# FlashLight.net
KiCad netlist of a schematic drawn in EAGLE
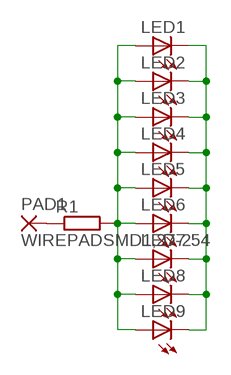
[diagram p0: schematic, sheet 1]

(export (version "E")
  (design (tool "Eeschema 10.0.6"))
  (components
    (comp (ref "LED1")
      (value "LED5MM")
      (footprint "eagle-import:LED5MM")
      (libsource (lib "eagle-import") (part "LED5MM"))
    )
    (comp (ref "LED2")
      (value "LED5MM")
      (footprint "eagle-import:LED5MM")
      (libsource (lib "eagle-import") (part "LED5MM"))
    )
    (comp (ref "LED3")
      (value "LED5MM")
      (footprint "eagle-import:LED5MM")
      (libsource (lib "eagle-import") (part "LED5MM"))
    )
    (comp (ref "LED4")
      (value "LED5MM")
      (footprint "eagle-import:LED5MM")
      (libsource (lib "eagle-import") (part "LED5MM"))
    )
    (comp (ref "LED5")
      (value "LED5MM")
      (footprint "eagle-import:LED5MM")
      (libsource (lib "eagle-import") (part "LED5MM"))
    )
    (comp (ref "LED6")
      (value "LED5MM")
      (footprint "eagle-import:LED5MM")
      (libsource (lib "eagle-import") (part "LED5MM"))
    )
    (comp (ref "LED7")
      (value "LED5MM")
      (footprint "eagle-import:LED5MM")
      (libsource (lib "eagle-import") (part "LED5MM"))
    )
    (comp (ref "LED8")
      (value "LED5MM")
      (footprint "eagle-import:LED5MM")
      (libsource (lib "eagle-import") (part "LED5MM"))
    )
    (comp (ref "LED9")
      (value "LED5MM")
      (footprint "eagle-import:LED5MM")
      (libsource (lib "eagle-import") (part "LED5MM"))
    )
    (comp (ref "PAD1")
      (value "WIREPADSMD1,27-254")
      (footprint "eagle-import:SMD1,27-2,54")
      (libsource (lib "eagle-import") (part "WIREPADSMD1,27-254"))
    )
    (comp (ref "R1")
      (value "R-EU_R1206")
      (footprint "eagle-import:R1206")
      (libsource (lib "eagle-import") (part "R-EU_R1206"))
    )
  )
  (nets
    (net (code "1") (name "Net-(LED1-C)") (class "Default")
      (node (ref "LED1") (pin "K") (pinfunction "C_K") (pintype "passive"))
      (node (ref "LED2") (pin "K") (pinfunction "C_K") (pintype "passive"))
      (node (ref "LED3") (pin "K") (pinfunction "C_K") (pintype "passive"))
      (node (ref "LED4") (pin "K") (pinfunction "C_K") (pintype "passive"))
      (node (ref "LED5") (pin "K") (pinfunction "C_K") (pintype "passive"))
      (node (ref "LED6") (pin "K") (pinfunction "C_K") (pintype "passive"))
      (node (ref "LED7") (pin "K") (pinfunction "C_K") (pintype "passive"))
      (node (ref "LED8") (pin "K") (pinfunction "C_K") (pintype "passive"))
      (node (ref "LED9") (pin "K") (pinfunction "C_K") (pintype "passive"))
    )
    (net (code "2") (name "Net-(LED1-PadA)") (class "Default")
      (node (ref "LED1") (pin "A") (pinfunction "A_A") (pintype "passive"))
      (node (ref "LED2") (pin "A") (pinfunction "A_A") (pintype "passive"))
      (node (ref "LED3") (pin "A") (pinfunction "A_A") (pintype "passive"))
      (node (ref "LED4") (pin "A") (pinfunction "A_A") (pintype "passive"))
      (node (ref "LED5") (pin "A") (pinfunction "A_A") (pintype "passive"))
      (node (ref "LED6") (pin "A") (pinfunction "A_A") (pintype "passive"))
      (node (ref "LED7") (pin "A") (pinfunction "A_A") (pintype "passive"))
      (node (ref "LED8") (pin "A") (pinfunction "A_A") (pintype "passive"))
      (node (ref "LED9") (pin "A") (pinfunction "A_A") (pintype "passive"))
      (node (ref "R1") (pin "2") (pinfunction "2_2") (pintype "passive"))
    )
    (net (code "3") (name "Net-(PAD1-P)") (class "Default")
      (node (ref "PAD1") (pin "1") (pinfunction "P_1") (pintype "passive"))
      (node (ref "R1") (pin "1") (pinfunction "1_1") (pintype "passive"))
    )
  )
)
